# NealEL2MOCOPTOS.net
KiCad netlist of a schematic drawn in EAGLE
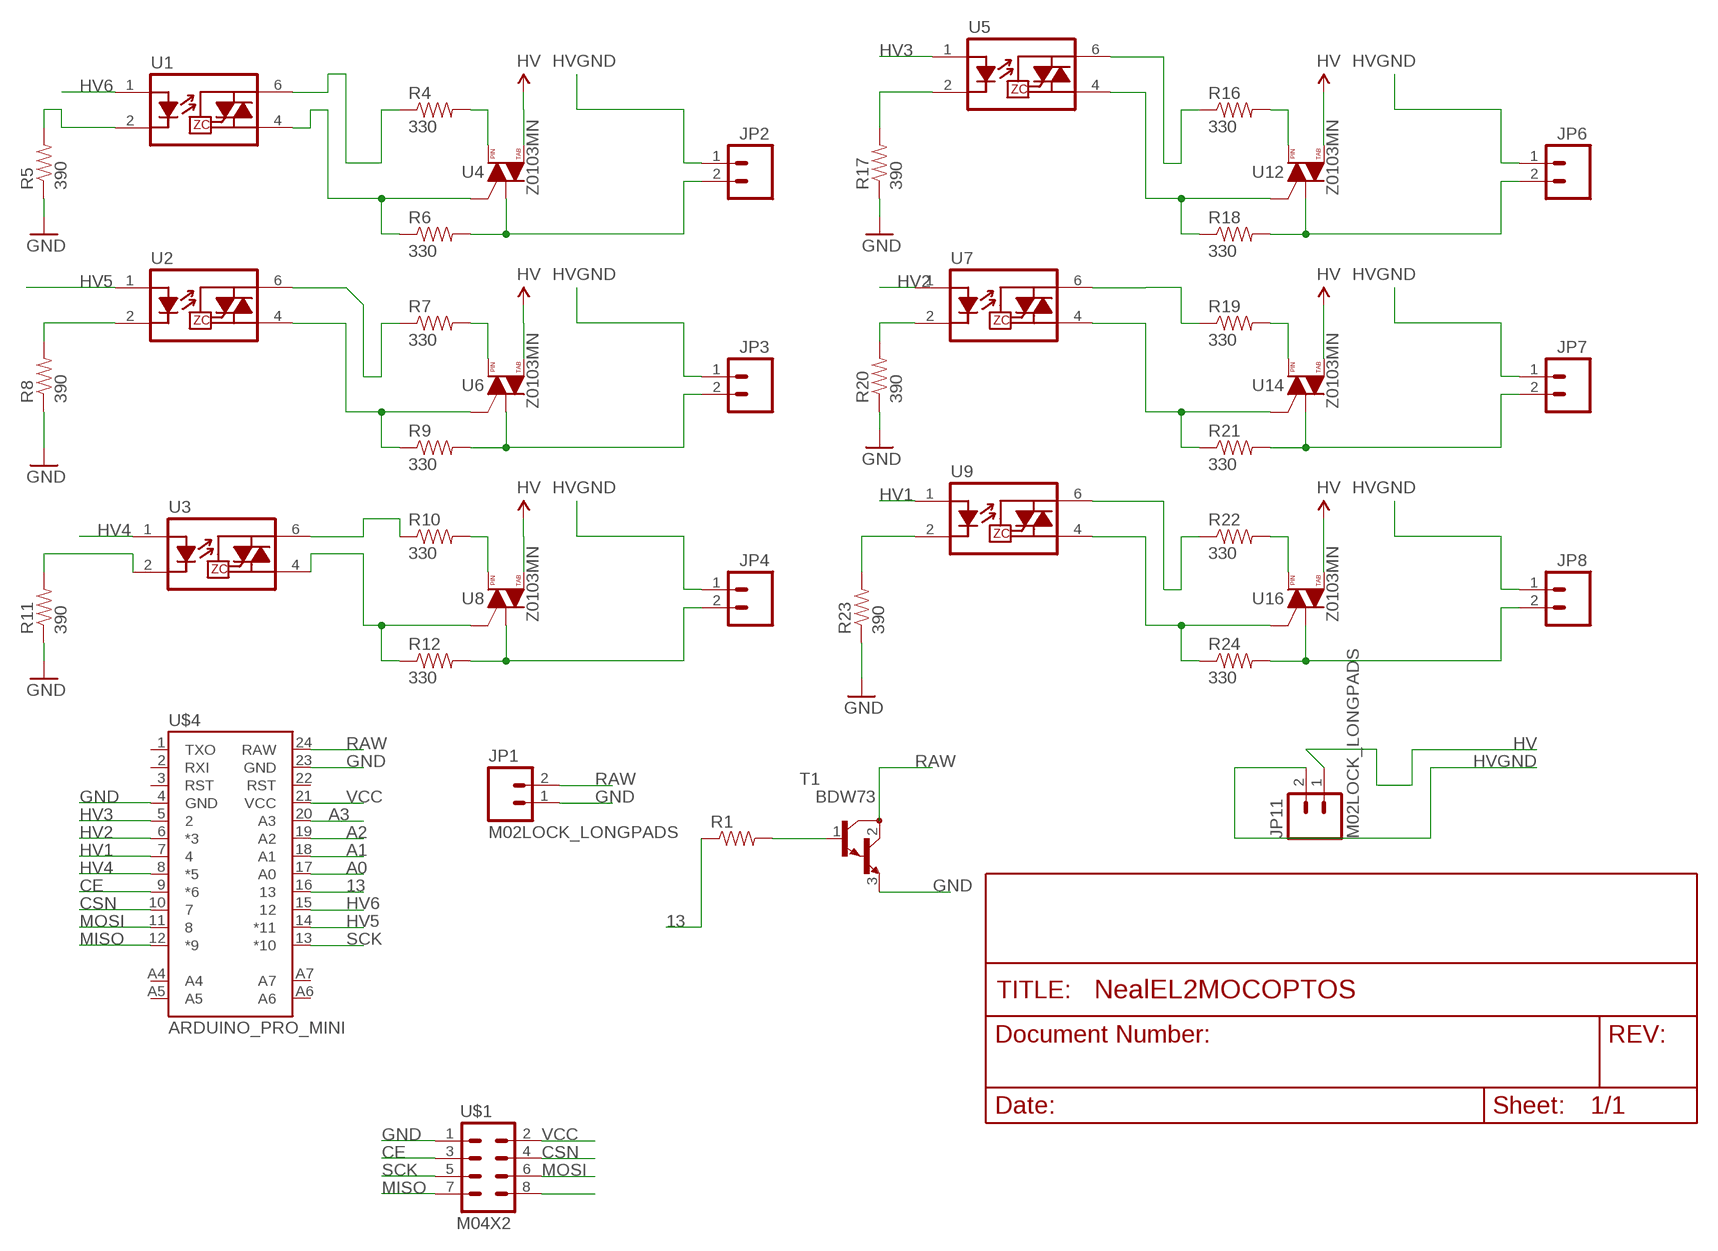
[diagram p0: schematic, sheet 1]

(export (version "E")
  (design (tool "Eeschema 10.0.6"))
  (components
    (comp (ref "JP1")
      (value "M02LOCK_LONGPADS")
      (footprint "eagle-import:1X02_LOCK_LONGPADS")
      (libsource (lib "eagle-import") (part "SparkFun-Connectors_M02LOCK_LONGPADS"))
    )
    (comp (ref "JP2")
      (value "M02PTH")
      (footprint "eagle-import:1X02")
      (libsource (lib "eagle-import") (part "M02PTH"))
    )
    (comp (ref "JP3")
      (value "M02PTH")
      (footprint "eagle-import:1X02")
      (libsource (lib "eagle-import") (part "M02PTH"))
    )
    (comp (ref "JP4")
      (value "M02PTH")
      (footprint "eagle-import:1X02")
      (libsource (lib "eagle-import") (part "M02PTH"))
    )
    (comp (ref "JP6")
      (value "M02PTH")
      (footprint "eagle-import:1X02")
      (libsource (lib "eagle-import") (part "M02PTH"))
    )
    (comp (ref "JP7")
      (value "M02PTH")
      (footprint "eagle-import:1X02")
      (libsource (lib "eagle-import") (part "M02PTH"))
    )
    (comp (ref "JP8")
      (value "M02PTH")
      (footprint "eagle-import:1X02")
      (libsource (lib "eagle-import") (part "M02PTH"))
    )
    (comp (ref "JP11")
      (value "M02LOCK_LONGPADS")
      (footprint "eagle-import:1X02_LOCK_LONGPADS")
      (libsource (lib "eagle-import") (part "SparkFun-Connectors_M02LOCK_LONGPADS"))
    )
    (comp (ref "R1")
      (value "RESISTORPTH-1/2W")
      (footprint "eagle-import:AXIAL-0.5")
      (libsource (lib "eagle-import") (part "SparkFun-Resistors_RESISTORPTH-1/2W"))
    )
    (comp (ref "R4")
      (value "330")
      (footprint "eagle-import:0603-RES")
      (libsource (lib "eagle-import") (part "RESISTOR0603-RES"))
    )
    (comp (ref "R5")
      (value "390")
      (footprint "eagle-import:0603-RES")
      (libsource (lib "eagle-import") (part "RESISTOR0603-RES"))
    )
    (comp (ref "R6")
      (value "330")
      (footprint "eagle-import:0603-RES")
      (libsource (lib "eagle-import") (part "RESISTOR0603-RES"))
    )
    (comp (ref "R7")
      (value "330")
      (footprint "eagle-import:0603-RES")
      (libsource (lib "eagle-import") (part "RESISTOR0603-RES"))
    )
    (comp (ref "R8")
      (value "390")
      (footprint "eagle-import:0603-RES")
      (libsource (lib "eagle-import") (part "RESISTOR0603-RES"))
    )
    (comp (ref "R9")
      (value "330")
      (footprint "eagle-import:0603-RES")
      (libsource (lib "eagle-import") (part "RESISTOR0603-RES"))
    )
    (comp (ref "R10")
      (value "330")
      (footprint "eagle-import:0603-RES")
      (libsource (lib "eagle-import") (part "RESISTOR0603-RES"))
    )
    (comp (ref "R11")
      (value "390")
      (footprint "eagle-import:0603-RES")
      (libsource (lib "eagle-import") (part "RESISTOR0603-RES"))
    )
    (comp (ref "R12")
      (value "330")
      (footprint "eagle-import:0603-RES")
      (libsource (lib "eagle-import") (part "RESISTOR0603-RES"))
    )
    (comp (ref "R16")
      (value "330")
      (footprint "eagle-import:0603-RES")
      (libsource (lib "eagle-import") (part "RESISTOR0603-RES"))
    )
    (comp (ref "R17")
      (value "390")
      (footprint "eagle-import:0603-RES")
      (libsource (lib "eagle-import") (part "RESISTOR0603-RES"))
    )
    (comp (ref "R18")
      (value "330")
      (footprint "eagle-import:0603-RES")
      (libsource (lib "eagle-import") (part "RESISTOR0603-RES"))
    )
    (comp (ref "R19")
      (value "330")
      (footprint "eagle-import:0603-RES")
      (libsource (lib "eagle-import") (part "RESISTOR0603-RES"))
    )
    (comp (ref "R20")
      (value "390")
      (footprint "eagle-import:0603-RES")
      (libsource (lib "eagle-import") (part "RESISTOR0603-RES"))
    )
    (comp (ref "R21")
      (value "330")
      (footprint "eagle-import:0603-RES")
      (libsource (lib "eagle-import") (part "RESISTOR0603-RES"))
    )
    (comp (ref "R22")
      (value "330")
      (footprint "eagle-import:0603-RES")
      (libsource (lib "eagle-import") (part "RESISTOR0603-RES"))
    )
    (comp (ref "R23")
      (value "390")
      (footprint "eagle-import:0603-RES")
      (libsource (lib "eagle-import") (part "RESISTOR0603-RES"))
    )
    (comp (ref "R24")
      (value "330")
      (footprint "eagle-import:0603-RES")
      (libsource (lib "eagle-import") (part "RESISTOR0603-RES"))
    )
    (comp (ref "T1")
      (value "BDW73")
      (footprint "eagle-import:TO220")
      (libsource (lib "eagle-import") (part "BDW73"))
    )
    (comp (ref "U$1")
      (value "M04X2")
      (footprint "eagle-import:2X4")
      (libsource (lib "eagle-import") (part "M04X2"))
    )
    (comp (ref "U$4")
      (value "ARDUINO_PRO_MINI")
      (footprint "eagle-import:ARDUINO_PRO_MINI")
      (libsource (lib "eagle-import") (part "ARDUINO_PRO_MINI"))
    )
    (comp (ref "U1")
      (value "MOC3063S")
      (footprint "eagle-import:DIP8SMD")
      (libsource (lib "eagle-import") (part "MOC3063S"))
    )
    (comp (ref "U2")
      (value "MOC3063S")
      (footprint "eagle-import:DIP8SMD")
      (libsource (lib "eagle-import") (part "MOC3063S"))
    )
    (comp (ref "U3")
      (value "MOC3063S")
      (footprint "eagle-import:DIP8SMD")
      (libsource (lib "eagle-import") (part "MOC3063S"))
    )
    (comp (ref "U4")
      (value "Z0103MN")
      (footprint "eagle-import:SOT223")
      (libsource (lib "eagle-import") (part "TRIACSMD"))
    )
    (comp (ref "U5")
      (value "MOC3063S")
      (footprint "eagle-import:DIP8SMD")
      (libsource (lib "eagle-import") (part "MOC3063S"))
    )
    (comp (ref "U6")
      (value "Z0103MN")
      (footprint "eagle-import:SOT223")
      (libsource (lib "eagle-import") (part "TRIACSMD"))
    )
    (comp (ref "U7")
      (value "MOC3063S")
      (footprint "eagle-import:DIP8SMD")
      (libsource (lib "eagle-import") (part "MOC3063S"))
    )
    (comp (ref "U8")
      (value "Z0103MN")
      (footprint "eagle-import:SOT223")
      (libsource (lib "eagle-import") (part "TRIACSMD"))
    )
    (comp (ref "U9")
      (value "MOC3063S")
      (footprint "eagle-import:DIP8SMD")
      (libsource (lib "eagle-import") (part "MOC3063S"))
    )
    (comp (ref "U12")
      (value "Z0103MN")
      (footprint "eagle-import:SOT223")
      (libsource (lib "eagle-import") (part "TRIACSMD"))
    )
    (comp (ref "U14")
      (value "Z0103MN")
      (footprint "eagle-import:SOT223")
      (libsource (lib "eagle-import") (part "TRIACSMD"))
    )
    (comp (ref "U16")
      (value "Z0103MN")
      (footprint "eagle-import:SOT223")
      (libsource (lib "eagle-import") (part "TRIACSMD"))
    )
  )
  (nets
    (net (code "1") (name "/13") (class "Default")
      (node (ref "R1") (pin "P$1") (pinfunction "1_P$1") (pintype "passive"))
      (node (ref "U$4") (pin "16") (pinfunction "13_16") (pintype "bidirectional"))
    )
    (net (code "2") (name "/A0") (class "Default")
      (node (ref "U$4") (pin "17") (pinfunction "A0_17") (pintype "bidirectional"))
    )
    (net (code "3") (name "/A1") (class "Default")
      (node (ref "U$4") (pin "18") (pinfunction "A1_18") (pintype "bidirectional"))
    )
    (net (code "4") (name "/A2") (class "Default")
      (node (ref "U$4") (pin "19") (pinfunction "A2_19") (pintype "bidirectional"))
    )
    (net (code "5") (name "/A3") (class "Default")
      (node (ref "U$4") (pin "20") (pinfunction "A3_20") (pintype "bidirectional"))
    )
    (net (code "6") (name "/CE") (class "Default")
      (node (ref "U$1") (pin "3") (pinfunction "3_3") (pintype "passive"))
      (node (ref "U$4") (pin "9") (pinfunction "*6_9") (pintype "bidirectional"))
    )
    (net (code "7") (name "/CSN") (class "Default")
      (node (ref "U$1") (pin "4") (pinfunction "4_4") (pintype "passive"))
      (node (ref "U$4") (pin "10") (pinfunction "7_10") (pintype "bidirectional"))
    )
    (net (code "8") (name "/HV1") (class "Default")
      (node (ref "U$4") (pin "7") (pinfunction "4_7") (pintype "bidirectional"))
      (node (ref "U9") (pin "1") (pinfunction "A_1") (pintype "bidirectional"))
    )
    (net (code "9") (name "/HV2") (class "Default")
      (node (ref "U$4") (pin "6") (pinfunction "*3_6") (pintype "bidirectional"))
      (node (ref "U7") (pin "1") (pinfunction "A_1") (pintype "bidirectional"))
    )
    (net (code "10") (name "/HV3") (class "Default")
      (node (ref "U$4") (pin "5") (pinfunction "2_5") (pintype "bidirectional"))
      (node (ref "U5") (pin "1") (pinfunction "A_1") (pintype "bidirectional"))
    )
    (net (code "11") (name "/HV4") (class "Default")
      (node (ref "U$4") (pin "8") (pinfunction "*5_8") (pintype "bidirectional"))
      (node (ref "U3") (pin "1") (pinfunction "A_1") (pintype "bidirectional"))
    )
    (net (code "12") (name "/HV5") (class "Default")
      (node (ref "U$4") (pin "14") (pinfunction "*11_14") (pintype "bidirectional"))
      (node (ref "U2") (pin "1") (pinfunction "A_1") (pintype "bidirectional"))
    )
    (net (code "13") (name "/HV6") (class "Default")
      (node (ref "U$4") (pin "15") (pinfunction "12_15") (pintype "bidirectional"))
      (node (ref "U1") (pin "1") (pinfunction "A_1") (pintype "bidirectional"))
    )
    (net (code "14") (name "/HVGND") (class "Default")
      (node (ref "JP11") (pin "2") (pinfunction "2_2") (pintype "passive"))
      (node (ref "JP2") (pin "1") (pinfunction "1_1") (pintype "passive"))
      (node (ref "JP3") (pin "1") (pinfunction "1_1") (pintype "passive"))
      (node (ref "JP4") (pin "1") (pinfunction "1_1") (pintype "passive"))
      (node (ref "JP6") (pin "1") (pinfunction "1_1") (pintype "passive"))
      (node (ref "JP7") (pin "1") (pinfunction "1_1") (pintype "passive"))
      (node (ref "JP8") (pin "1") (pinfunction "1_1") (pintype "passive"))
    )
    (net (code "15") (name "/MISO") (class "Default")
      (node (ref "U$1") (pin "7") (pinfunction "7_7") (pintype "passive"))
      (node (ref "U$4") (pin "12") (pinfunction "*9_12") (pintype "bidirectional"))
    )
    (net (code "16") (name "/MOSI") (class "Default")
      (node (ref "U$1") (pin "6") (pinfunction "6_6") (pintype "passive"))
      (node (ref "U$4") (pin "11") (pinfunction "8_11") (pintype "bidirectional"))
    )
    (net (code "17") (name "/RAW") (class "Default")
      (node (ref "JP1") (pin "2") (pinfunction "2_2") (pintype "passive"))
      (node (ref "T1") (pin "2") (pinfunction "C_2") (pintype "passive"))
      (node (ref "U$4") (pin "24") (pinfunction "RAW_24") (pintype "bidirectional"))
    )
    (net (code "18") (name "/SCK") (class "Default")
      (node (ref "U$1") (pin "5") (pinfunction "5_5") (pintype "passive"))
      (node (ref "U$4") (pin "13") (pinfunction "*10_13") (pintype "bidirectional"))
    )
    (net (code "19") (name "/VCC") (class "Default")
      (node (ref "U$1") (pin "2") (pinfunction "2_2") (pintype "passive"))
      (node (ref "U$4") (pin "21") (pinfunction "VCC_21") (pintype "bidirectional"))
    )
    (net (code "20") (name "GND") (class "Default")
      (node (ref "JP1") (pin "1") (pinfunction "1_1") (pintype "passive"))
      (node (ref "R11") (pin "1") (pinfunction "1_1") (pintype "passive"))
      (node (ref "R17") (pin "1") (pinfunction "1_1") (pintype "passive"))
      (node (ref "R20") (pin "1") (pinfunction "1_1") (pintype "passive"))
      (node (ref "R23") (pin "1") (pinfunction "1_1") (pintype "passive"))
      (node (ref "R5") (pin "1") (pinfunction "1_1") (pintype "passive"))
      (node (ref "R8") (pin "1") (pinfunction "1_1") (pintype "passive"))
      (node (ref "T1") (pin "3") (pinfunction "E_3") (pintype "passive"))
      (node (ref "U$1") (pin "1") (pinfunction "1_1") (pintype "passive"))
      (node (ref "U$4") (pin "23") (pinfunction "GND_23") (pintype "bidirectional"))
      (node (ref "U$4") (pin "4") (pinfunction "GND_4") (pintype "bidirectional"))
    )
    (net (code "21") (name "HV") (class "Default")
      (node (ref "JP11") (pin "1") (pinfunction "1_1") (pintype "passive"))
      (node (ref "U12") (pin "4") (pinfunction "T2_4") (pintype "passive"))
      (node (ref "U14") (pin "4") (pinfunction "T2_4") (pintype "passive"))
      (node (ref "U16") (pin "4") (pinfunction "T2_4") (pintype "passive"))
      (node (ref "U4") (pin "4") (pinfunction "T2_4") (pintype "passive"))
      (node (ref "U6") (pin "4") (pinfunction "T2_4") (pintype "passive"))
      (node (ref "U8") (pin "4") (pinfunction "T2_4") (pintype "passive"))
    )
    (net (code "22") (name "Net-(R1-2)") (class "Default")
      (node (ref "R1") (pin "P$2") (pinfunction "2_P$2") (pintype "passive"))
      (node (ref "T1") (pin "1") (pinfunction "B_1") (pintype "passive"))
    )
    (net (code "23") (name "Net-(R4-Pad2)") (class "Default")
      (node (ref "R4") (pin "2") (pinfunction "2_2") (pintype "passive"))
      (node (ref "U4") (pin "2") (pinfunction "T2_2") (pintype "passive"))
    )
    (net (code "24") (name "Net-(R7-Pad2)") (class "Default")
      (node (ref "R7") (pin "2") (pinfunction "2_2") (pintype "passive"))
      (node (ref "U6") (pin "2") (pinfunction "T2_2") (pintype "passive"))
    )
    (net (code "25") (name "Net-(R10-Pad2)") (class "Default")
      (node (ref "R10") (pin "2") (pinfunction "2_2") (pintype "passive"))
      (node (ref "U8") (pin "2") (pinfunction "T2_2") (pintype "passive"))
    )
    (net (code "26") (name "Net-(R16-Pad2)") (class "Default")
      (node (ref "R16") (pin "2") (pinfunction "2_2") (pintype "passive"))
      (node (ref "U12") (pin "2") (pinfunction "T2_2") (pintype "passive"))
    )
    (net (code "27") (name "Net-(R19-Pad2)") (class "Default")
      (node (ref "R19") (pin "2") (pinfunction "2_2") (pintype "passive"))
      (node (ref "U14") (pin "2") (pinfunction "T2_2") (pintype "passive"))
    )
    (net (code "28") (name "Net-(R22-Pad2)") (class "Default")
      (node (ref "R22") (pin "2") (pinfunction "2_2") (pintype "passive"))
      (node (ref "U16") (pin "2") (pinfunction "T2_2") (pintype "passive"))
    )
    (net (code "29") (name "Net-(U1-K)") (class "Default")
      (node (ref "R5") (pin "2") (pinfunction "2_2") (pintype "passive"))
      (node (ref "U1") (pin "2") (pinfunction "K_2") (pintype "bidirectional"))
    )
    (net (code "30") (name "Net-(U1-T1)") (class "Default")
      (node (ref "R4") (pin "1") (pinfunction "1_1") (pintype "passive"))
      (node (ref "U1") (pin "6") (pinfunction "T1_6") (pintype "bidirectional"))
    )
    (net (code "31") (name "Net-(U1-T2)") (class "Default")
      (node (ref "R6") (pin "1") (pinfunction "1_1") (pintype "passive"))
      (node (ref "U1") (pin "4") (pinfunction "T2_4") (pintype "bidirectional"))
      (node (ref "U4") (pin "3") (pinfunction "G_3") (pintype "bidirectional"))
    )
    (net (code "32") (name "Net-(U2-K)") (class "Default")
      (node (ref "R8") (pin "2") (pinfunction "2_2") (pintype "passive"))
      (node (ref "U2") (pin "2") (pinfunction "K_2") (pintype "bidirectional"))
    )
    (net (code "33") (name "Net-(U2-T1)") (class "Default")
      (node (ref "R7") (pin "1") (pinfunction "1_1") (pintype "passive"))
      (node (ref "U2") (pin "6") (pinfunction "T1_6") (pintype "bidirectional"))
    )
    (net (code "34") (name "Net-(U2-T2)") (class "Default")
      (node (ref "R9") (pin "1") (pinfunction "1_1") (pintype "passive"))
      (node (ref "U2") (pin "4") (pinfunction "T2_4") (pintype "bidirectional"))
      (node (ref "U6") (pin "3") (pinfunction "G_3") (pintype "bidirectional"))
    )
    (net (code "35") (name "Net-(U3-K)") (class "Default")
      (node (ref "R11") (pin "2") (pinfunction "2_2") (pintype "passive"))
      (node (ref "U3") (pin "2") (pinfunction "K_2") (pintype "bidirectional"))
    )
    (net (code "36") (name "Net-(U3-T1)") (class "Default")
      (node (ref "R10") (pin "1") (pinfunction "1_1") (pintype "passive"))
      (node (ref "U3") (pin "6") (pinfunction "T1_6") (pintype "bidirectional"))
    )
    (net (code "37") (name "Net-(U3-T2)") (class "Default")
      (node (ref "R12") (pin "1") (pinfunction "1_1") (pintype "passive"))
      (node (ref "U3") (pin "4") (pinfunction "T2_4") (pintype "bidirectional"))
      (node (ref "U8") (pin "3") (pinfunction "G_3") (pintype "bidirectional"))
    )
    (net (code "38") (name "Net-(U4-T1)") (class "Default")
      (node (ref "JP2") (pin "2") (pinfunction "2_2") (pintype "passive"))
      (node (ref "R6") (pin "2") (pinfunction "2_2") (pintype "passive"))
      (node (ref "U4") (pin "1") (pinfunction "T1_1") (pintype "bidirectional"))
    )
    (net (code "39") (name "Net-(U5-K)") (class "Default")
      (node (ref "R17") (pin "2") (pinfunction "2_2") (pintype "passive"))
      (node (ref "U5") (pin "2") (pinfunction "K_2") (pintype "bidirectional"))
    )
    (net (code "40") (name "Net-(U5-T1)") (class "Default")
      (node (ref "R16") (pin "1") (pinfunction "1_1") (pintype "passive"))
      (node (ref "U5") (pin "6") (pinfunction "T1_6") (pintype "bidirectional"))
    )
    (net (code "41") (name "Net-(U6-T1)") (class "Default")
      (node (ref "JP3") (pin "2") (pinfunction "2_2") (pintype "passive"))
      (node (ref "R9") (pin "2") (pinfunction "2_2") (pintype "passive"))
      (node (ref "U6") (pin "1") (pinfunction "T1_1") (pintype "bidirectional"))
    )
    (net (code "42") (name "Net-(U7-K)") (class "Default")
      (node (ref "R20") (pin "2") (pinfunction "2_2") (pintype "passive"))
      (node (ref "U7") (pin "2") (pinfunction "K_2") (pintype "bidirectional"))
    )
    (net (code "43") (name "Net-(U7-T1)") (class "Default")
      (node (ref "R19") (pin "1") (pinfunction "1_1") (pintype "passive"))
      (node (ref "U7") (pin "6") (pinfunction "T1_6") (pintype "bidirectional"))
    )
    (net (code "44") (name "Net-(U8-T1)") (class "Default")
      (node (ref "JP4") (pin "2") (pinfunction "2_2") (pintype "passive"))
      (node (ref "R12") (pin "2") (pinfunction "2_2") (pintype "passive"))
      (node (ref "U8") (pin "1") (pinfunction "T1_1") (pintype "bidirectional"))
    )
    (net (code "45") (name "Net-(U9-K)") (class "Default")
      (node (ref "R23") (pin "2") (pinfunction "2_2") (pintype "passive"))
      (node (ref "U9") (pin "2") (pinfunction "K_2") (pintype "bidirectional"))
    )
    (net (code "46") (name "Net-(U9-T1)") (class "Default")
      (node (ref "R22") (pin "1") (pinfunction "1_1") (pintype "passive"))
      (node (ref "U9") (pin "6") (pinfunction "T1_6") (pintype "bidirectional"))
    )
    (net (code "47") (name "Net-(U12-G)") (class "Default")
      (node (ref "R18") (pin "1") (pinfunction "1_1") (pintype "passive"))
      (node (ref "U12") (pin "3") (pinfunction "G_3") (pintype "bidirectional"))
      (node (ref "U5") (pin "4") (pinfunction "T2_4") (pintype "bidirectional"))
    )
    (net (code "48") (name "Net-(U12-T1)") (class "Default")
      (node (ref "JP6") (pin "2") (pinfunction "2_2") (pintype "passive"))
      (node (ref "R18") (pin "2") (pinfunction "2_2") (pintype "passive"))
      (node (ref "U12") (pin "1") (pinfunction "T1_1") (pintype "bidirectional"))
    )
    (net (code "49") (name "Net-(U14-G)") (class "Default")
      (node (ref "R21") (pin "1") (pinfunction "1_1") (pintype "passive"))
      (node (ref "U14") (pin "3") (pinfunction "G_3") (pintype "bidirectional"))
      (node (ref "U7") (pin "4") (pinfunction "T2_4") (pintype "bidirectional"))
    )
    (net (code "50") (name "Net-(U14-T1)") (class "Default")
      (node (ref "JP7") (pin "2") (pinfunction "2_2") (pintype "passive"))
      (node (ref "R21") (pin "2") (pinfunction "2_2") (pintype "passive"))
      (node (ref "U14") (pin "1") (pinfunction "T1_1") (pintype "bidirectional"))
    )
    (net (code "51") (name "Net-(U16-G)") (class "Default")
      (node (ref "R24") (pin "1") (pinfunction "1_1") (pintype "passive"))
      (node (ref "U16") (pin "3") (pinfunction "G_3") (pintype "bidirectional"))
      (node (ref "U9") (pin "4") (pinfunction "T2_4") (pintype "bidirectional"))
    )
    (net (code "52") (name "Net-(U16-T1)") (class "Default")
      (node (ref "JP8") (pin "2") (pinfunction "2_2") (pintype "passive"))
      (node (ref "R24") (pin "2") (pinfunction "2_2") (pintype "passive"))
      (node (ref "U16") (pin "1") (pinfunction "T1_1") (pintype "bidirectional"))
    )
    (net (code "53") (name "unconnected-(U$1-Pad8)") (class "Default")
      (node (ref "U$1") (pin "8") (pinfunction "8_8") (pintype "passive"))
    )
    (net (code "54") (name "unconnected-(U$4-PadA4)") (class "Default")
      (node (ref "U$4") (pin "A4") (pinfunction "A4_A4") (pintype "bidirectional"))
    )
    (net (code "55") (name "unconnected-(U$4-PadA5)") (class "Default")
      (node (ref "U$4") (pin "A5") (pinfunction "A5_A5") (pintype "bidirectional"))
    )
    (net (code "56") (name "unconnected-(U$4-PadA6)") (class "Default")
      (node (ref "U$4") (pin "A6") (pinfunction "A6_A6") (pintype "bidirectional"))
    )
    (net (code "57") (name "unconnected-(U$4-PadA7)") (class "Default")
      (node (ref "U$4") (pin "A7") (pinfunction "A7_A7") (pintype "bidirectional"))
    )
    (net (code "58") (name "unconnected-(U$4-RST-Pad3)") (class "Default")
      (node (ref "U$4") (pin "3") (pinfunction "RST_3") (pintype "bidirectional"))
    )
    (net (code "59") (name "unconnected-(U$4-RST-Pad22)") (class "Default")
      (node (ref "U$4") (pin "22") (pinfunction "RST_22") (pintype "bidirectional"))
    )
    (net (code "60") (name "unconnected-(U$4-RXI-Pad2)") (class "Default")
      (node (ref "U$4") (pin "2") (pinfunction "RXI_2") (pintype "bidirectional"))
    )
    (net (code "61") (name "unconnected-(U$4-TXO-Pad1)") (class "Default")
      (node (ref "U$4") (pin "1") (pinfunction "TXO_1") (pintype "bidirectional"))
    )
  )
)
